# roomba_led_pcb_v1.net
KiCad netlist of a schematic drawn in EAGLE
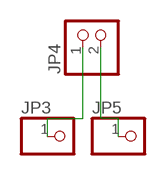
[diagram p0: schematic, sheet 1]

(export (version "E")
  (design (tool "Eeschema 10.0.6"))
  (components
    (comp (ref "JP3")
      (value "PINHD-1X1")
      (footprint "eagle-import:1X01")
      (libsource (lib "eagle-import") (part "PINHD-1X1"))
    )
    (comp (ref "JP4")
      (value "PINHD-1X2/90")
      (footprint "eagle-import:1X02_90")
      (libsource (lib "eagle-import") (part "PINHD-1X2/90"))
    )
    (comp (ref "JP5")
      (value "PINHD-1X1")
      (footprint "eagle-import:1X01")
      (libsource (lib "eagle-import") (part "PINHD-1X1"))
    )
  )
  (nets
    (net (code "1") (name "Net-(JP3-Pad1)") (class "Default")
      (node (ref "JP3") (pin "1") (pinfunction "1_1") (pintype "passive"))
      (node (ref "JP4") (pin "1") (pinfunction "1_1") (pintype "passive"))
    )
    (net (code "2") (name "Net-(JP4-Pad2)") (class "Default")
      (node (ref "JP4") (pin "2") (pinfunction "2_2") (pintype "passive"))
      (node (ref "JP5") (pin "1") (pinfunction "1_1") (pintype "passive"))
    )
  )
)
